# robotShield_Buttom.net
KiCad netlist of a schematic drawn in Altium Designer
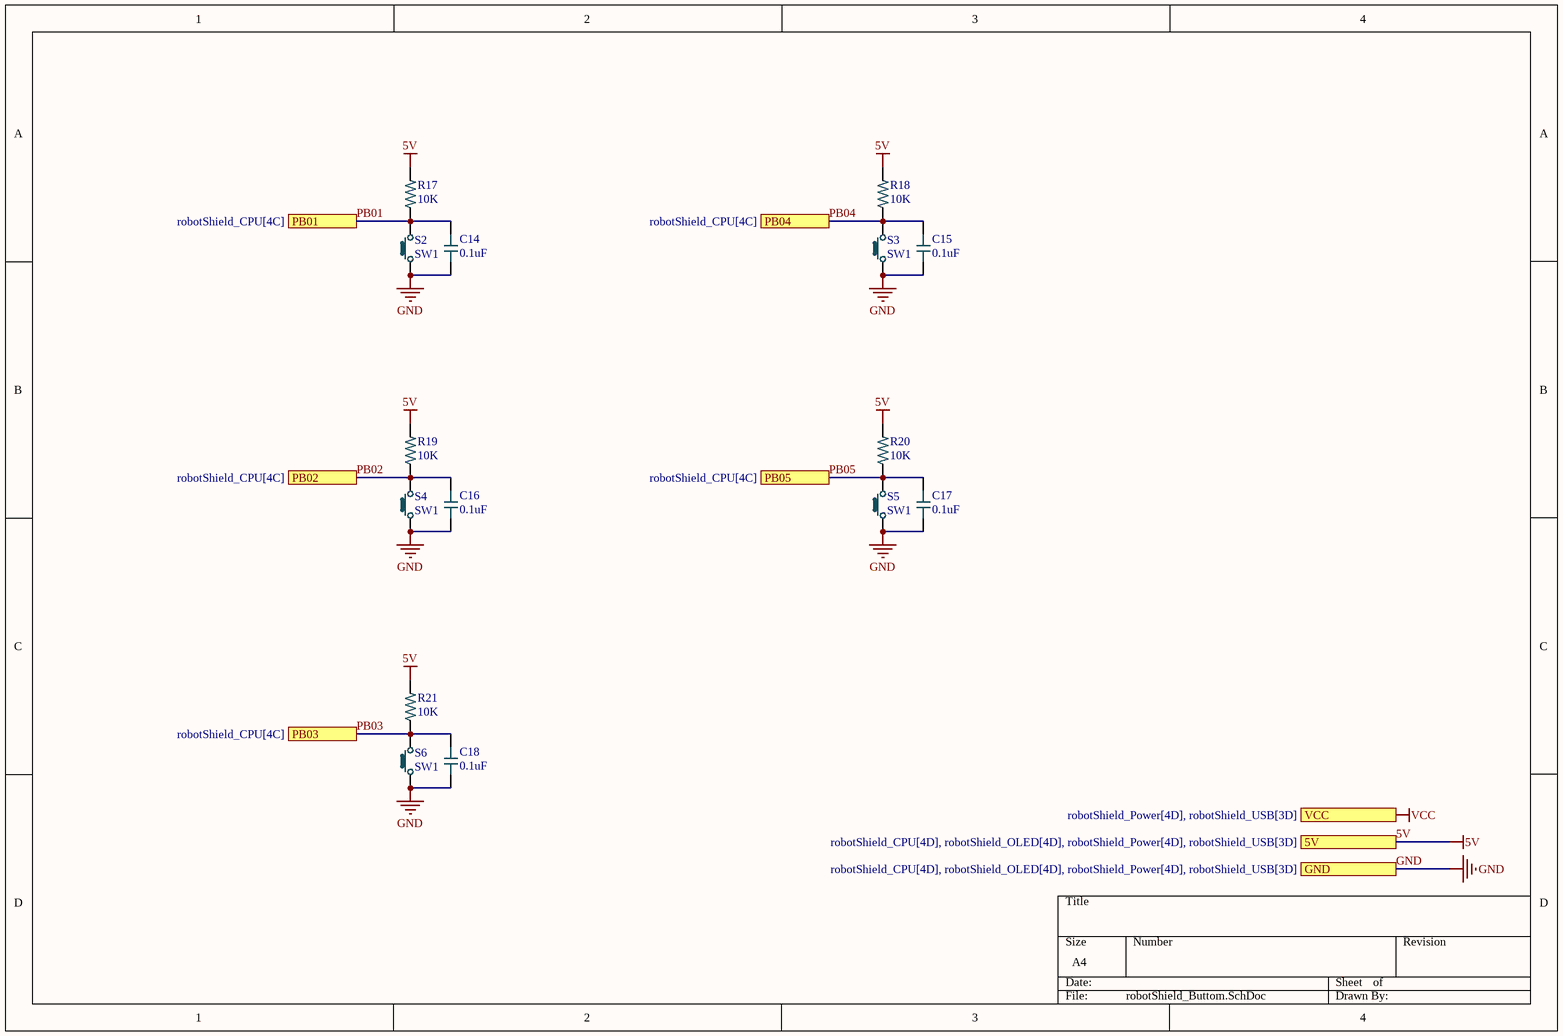
[diagram p0: robotShield_Buttom.SchDoc]

(export (version "E")
  (design (tool "Eeschema 10.0.6"))
  (components
    (comp (ref "C14")
      (value "0.1uF")
      (footprint "CAP0603")
      (description "CAP SMD")
      (fields (field (name "MF") "AVX") (field (name "MP") "LD031A101GAB2A"))
      (libsource (lib "Hossein72T") (part "Capacitor"))
    )
    (comp (ref "C15")
      (value "0.1uF")
      (footprint "CAP0603")
      (description "CAP SMD")
      (fields (field (name "MF") "AVX") (field (name "MP") "LD031A101GAB2A"))
      (libsource (lib "Hossein72T") (part "Capacitor"))
    )
    (comp (ref "C16")
      (value "0.1uF")
      (footprint "CAP0603")
      (description "CAP SMD")
      (fields (field (name "MF") "AVX") (field (name "MP") "LD031A101GAB2A"))
      (libsource (lib "Hossein72T") (part "Capacitor"))
    )
    (comp (ref "C17")
      (value "0.1uF")
      (footprint "CAP0603")
      (description "CAP SMD")
      (fields (field (name "MF") "AVX") (field (name "MP") "LD031A101GAB2A"))
      (libsource (lib "Hossein72T") (part "Capacitor"))
    )
    (comp (ref "C18")
      (value "0.1uF")
      (footprint "CAP0603")
      (description "CAP SMD")
      (fields (field (name "MF") "AVX") (field (name "MP") "LD031A101GAB2A"))
      (libsource (lib "Hossein72T") (part "Capacitor"))
    )
    (comp (ref "R17")
      (value "10K")
      (footprint "RES0603")
      (description "RES 0.27 OHM 1% 1/10W")
      (fields (field (name "MP") "3-1879460-5") (field (name "MF") "TE Connectivity"))
      (libsource (lib "Hossein72T") (part "Resistor"))
    )
    (comp (ref "R18")
      (value "10K")
      (footprint "RES0603")
      (description "RES 0.27 OHM 1% 1/10W")
      (fields (field (name "MP") "3-1879460-5") (field (name "MF") "TE Connectivity"))
      (libsource (lib "Hossein72T") (part "Resistor"))
    )
    (comp (ref "R19")
      (value "10K")
      (footprint "RES0603")
      (description "RES 0.27 OHM 1% 1/10W")
      (fields (field (name "MP") "3-1879460-5") (field (name "MF") "TE Connectivity"))
      (libsource (lib "Hossein72T") (part "Resistor"))
    )
    (comp (ref "R20")
      (value "10K")
      (footprint "RES0603")
      (description "RES 0.27 OHM 1% 1/10W")
      (fields (field (name "MP") "3-1879460-5") (field (name "MF") "TE Connectivity"))
      (libsource (lib "Hossein72T") (part "Resistor"))
    )
    (comp (ref "R21")
      (value "10K")
      (footprint "RES0603")
      (description "RES 0.27 OHM 1% 1/10W")
      (fields (field (name "MP") "3-1879460-5") (field (name "MF") "TE Connectivity"))
      (libsource (lib "Hossein72T") (part "Resistor"))
    )
    (comp (ref "S2")
      (value "SW1")
      (footprint "Pushbutton_Tactile")
      (description "Switch,Pushbutton,Tactile,SPST")
      (libsource (lib "Hossein72T") (part "Pushbutton"))
    )
    (comp (ref "S3")
      (value "SW1")
      (footprint "Pushbutton_Tactile")
      (description "Switch,Pushbutton,Tactile,SPST")
      (libsource (lib "Hossein72T") (part "Pushbutton"))
    )
    (comp (ref "S4")
      (value "SW1")
      (footprint "Pushbutton_Tactile")
      (description "Switch,Pushbutton,Tactile,SPST")
      (libsource (lib "Hossein72T") (part "Pushbutton"))
    )
    (comp (ref "S5")
      (value "SW1")
      (footprint "Pushbutton_Tactile")
      (description "Switch,Pushbutton,Tactile,SPST")
      (libsource (lib "Hossein72T") (part "Pushbutton"))
    )
    (comp (ref "S6")
      (value "SW1")
      (footprint "Pushbutton_Tactile")
      (description "Switch,Pushbutton,Tactile,SPST")
      (libsource (lib "Hossein72T") (part "Pushbutton"))
    )
  )
  (nets
    (net (code "1") (name "/PB01") (class "Default")
      (node (ref "C14") (pin "1") (pinfunction "1_1") (pintype "passive"))
      (node (ref "R17") (pin "1") (pinfunction "1_1") (pintype "passive"))
      (node (ref "S2") (pin "2") (pinfunction "2_2") (pintype "passive"))
    )
    (net (code "2") (name "/PB02") (class "Default")
      (node (ref "C16") (pin "1") (pinfunction "1_1") (pintype "passive"))
      (node (ref "R19") (pin "1") (pinfunction "1_1") (pintype "passive"))
      (node (ref "S4") (pin "2") (pinfunction "2_2") (pintype "passive"))
    )
    (net (code "3") (name "/PB03") (class "Default")
      (node (ref "C18") (pin "1") (pinfunction "1_1") (pintype "passive"))
      (node (ref "R21") (pin "1") (pinfunction "1_1") (pintype "passive"))
      (node (ref "S6") (pin "2") (pinfunction "2_2") (pintype "passive"))
    )
    (net (code "4") (name "/PB04") (class "Default")
      (node (ref "C15") (pin "1") (pinfunction "1_1") (pintype "passive"))
      (node (ref "R18") (pin "1") (pinfunction "1_1") (pintype "passive"))
      (node (ref "S3") (pin "2") (pinfunction "2_2") (pintype "passive"))
    )
    (net (code "5") (name "/PB05") (class "Default")
      (node (ref "C17") (pin "1") (pinfunction "1_1") (pintype "passive"))
      (node (ref "R20") (pin "1") (pinfunction "1_1") (pintype "passive"))
      (node (ref "S5") (pin "2") (pinfunction "2_2") (pintype "passive"))
    )
    (net (code "6") (name "5V") (class "Default")
      (node (ref "R17") (pin "2") (pinfunction "2_2") (pintype "passive"))
      (node (ref "R18") (pin "2") (pinfunction "2_2") (pintype "passive"))
      (node (ref "R19") (pin "2") (pinfunction "2_2") (pintype "passive"))
      (node (ref "R20") (pin "2") (pinfunction "2_2") (pintype "passive"))
      (node (ref "R21") (pin "2") (pinfunction "2_2") (pintype "passive"))
    )
    (net (code "7") (name "GND") (class "Default")
      (node (ref "C14") (pin "2") (pinfunction "2_2") (pintype "passive"))
      (node (ref "C15") (pin "2") (pinfunction "2_2") (pintype "passive"))
      (node (ref "C16") (pin "2") (pinfunction "2_2") (pintype "passive"))
      (node (ref "C17") (pin "2") (pinfunction "2_2") (pintype "passive"))
      (node (ref "C18") (pin "2") (pinfunction "2_2") (pintype "passive"))
      (node (ref "S2") (pin "1") (pinfunction "1_1") (pintype "passive"))
      (node (ref "S3") (pin "1") (pinfunction "1_1") (pintype "passive"))
      (node (ref "S4") (pin "1") (pinfunction "1_1") (pintype "passive"))
      (node (ref "S5") (pin "1") (pinfunction "1_1") (pintype "passive"))
      (node (ref "S6") (pin "1") (pinfunction "1_1") (pintype "passive"))
    )
  )
)
